# jpwr_v1.net
KiCad netlist of a schematic drawn in EAGLE
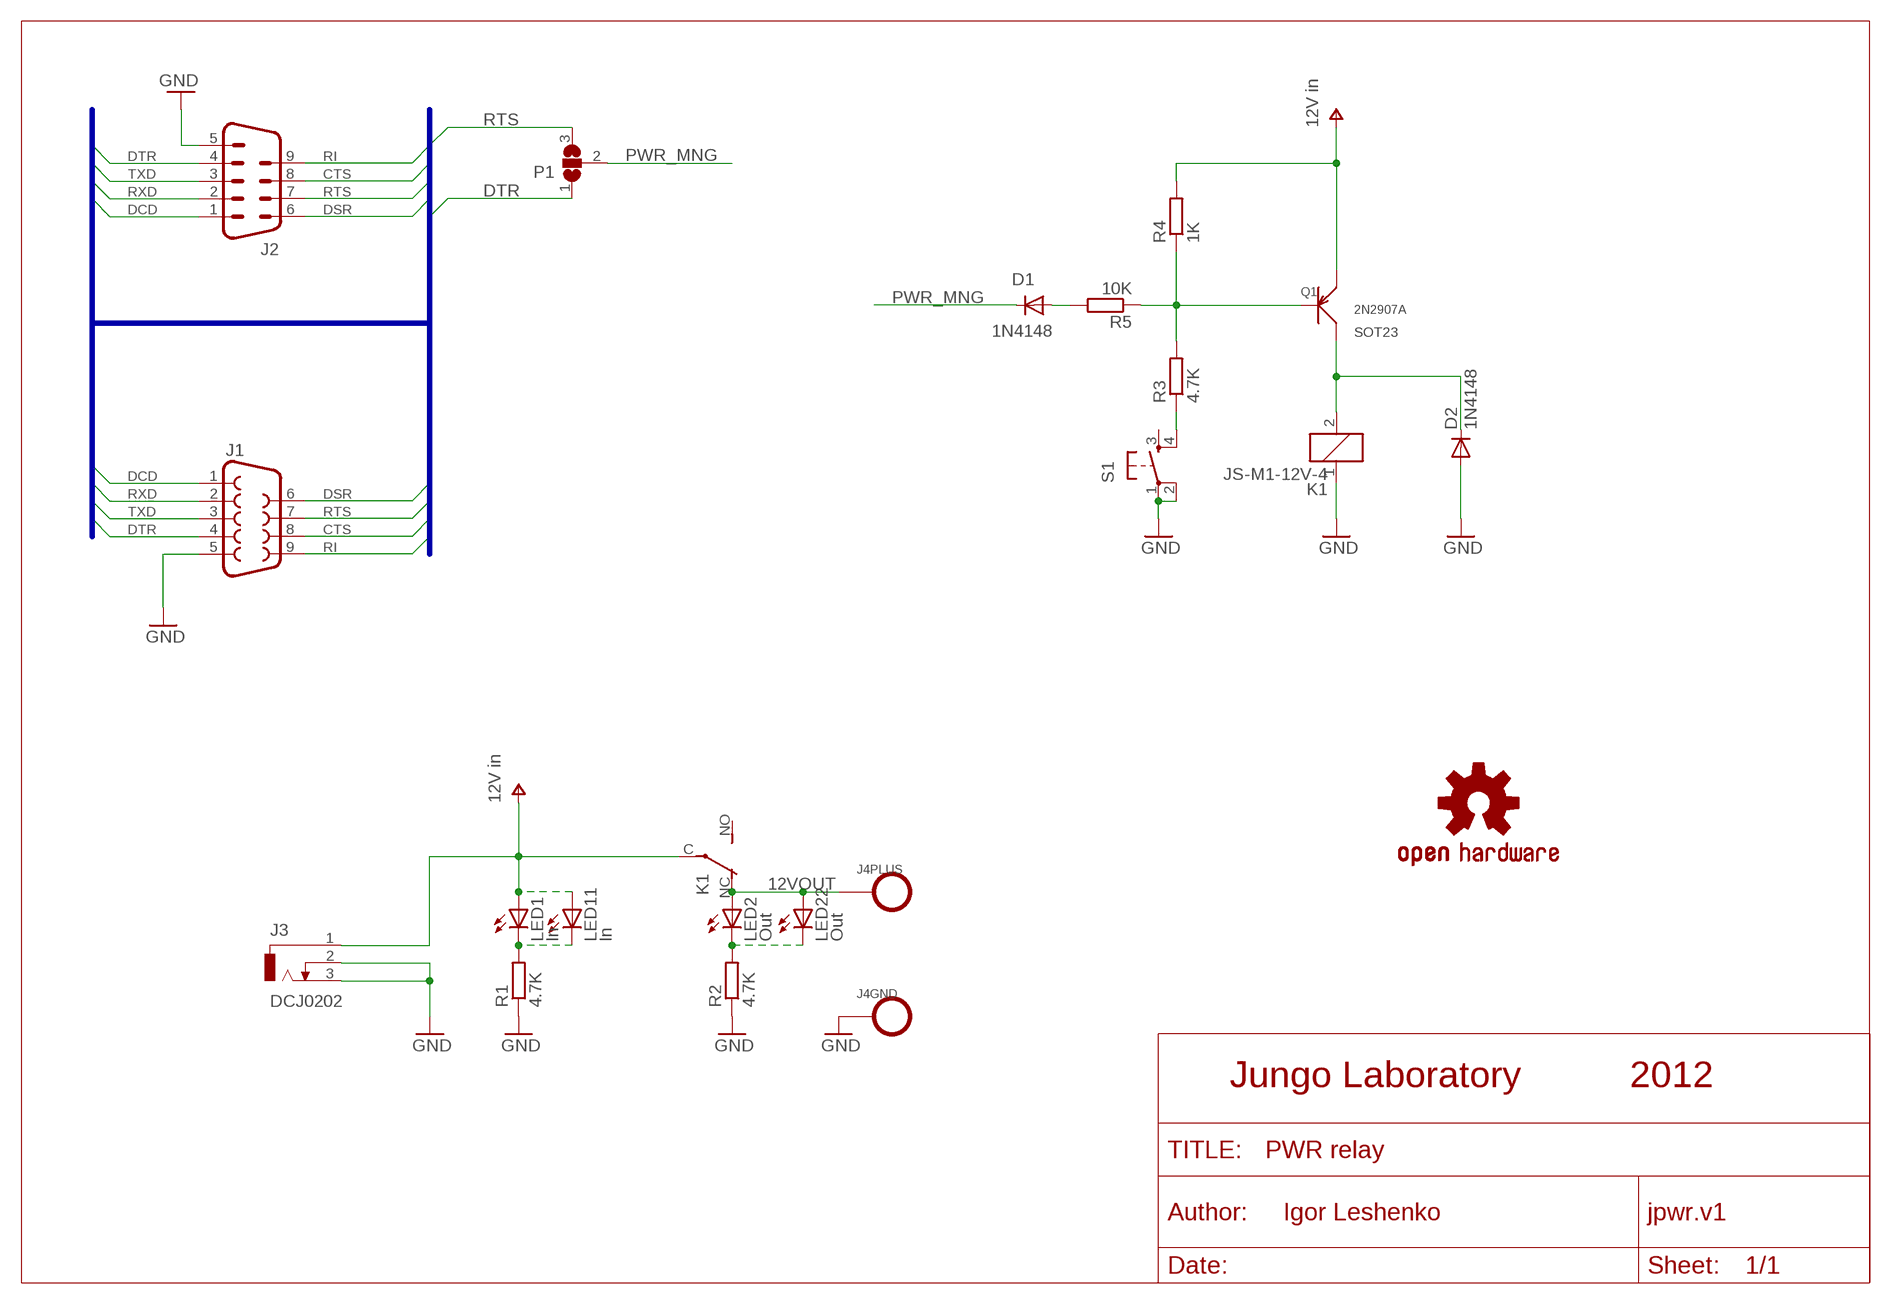
[diagram p0: schematic, sheet 1]

(export (version "E")
  (design (tool "Eeschema 10.0.6"))
  (components
    (comp (ref "D1")
      (value "1N4148")
      (footprint "eagle-import:SOD123")
      (libsource (lib "eagle-import") (part "DIODE-SOD123"))
    )
    (comp (ref "D2")
      (value "1N4148")
      (footprint "eagle-import:SOD123")
      (libsource (lib "eagle-import") (part "DIODE-SOD123"))
    )
    (comp (ref "J1")
      (value "F09D")
      (footprint "eagle-import:F09D")
      (libsource (lib "eagle-import") (part "F09D"))
    )
    (comp (ref "J2")
      (value "M09D")
      (footprint "eagle-import:M09D")
      (libsource (lib "eagle-import") (part "M09D"))
    )
    (comp (ref "J3")
      (value "DCJ0202")
      (footprint "eagle-import:DCJ0202")
      (libsource (lib "eagle-import") (part "DCJ0202"))
    )
    (comp (ref "J4")
      (value "POWER-OUT")
      (footprint "eagle-import:FLEX-POWER")
      (libsource (lib "eagle-import") (part "POWER-OUT"))
    )
    (comp (ref "K1")
      (value "JS-M1-12V-4")
      (footprint "eagle-import:SRD")
      (fields
        (field (name "MPN") "JSM1-12V-4")
        (field (name "MPN_1") "JSM1-12V-4")
        (field (name "OC_FARNELL") "910338")
        (field (name "OC_NEWARK") "13P4552")
      )
      (libsource (lib "eagle-import") (part "JS-M1-12V-4"))
    )
    (comp (ref "LED1")
      (value "In")
      (footprint "eagle-import:CHIP-LED0805")
      (libsource (lib "eagle-import") (part "LEDCHIP-LED0805"))
    )
    (comp (ref "LED2")
      (value "Out")
      (footprint "eagle-import:CHIP-LED0805")
      (libsource (lib "eagle-import") (part "LEDCHIP-LED0805"))
    )
    (comp (ref "LED11")
      (value "In")
      (footprint "eagle-import:CHIP-LED0805")
      (libsource (lib "eagle-import") (part "LEDCHIP-LED0805"))
    )
    (comp (ref "LED22")
      (value "Out")
      (footprint "eagle-import:CHIP-LED0805")
      (libsource (lib "eagle-import") (part "LEDCHIP-LED0805"))
    )
    (comp (ref "P1")
      (value "PAD-SOLDERJUMPER-2WAYT")
      (footprint "eagle-import:3P-SMD-4.8X2")
      (libsource (lib "eagle-import") (part "PAD-SOLDERJUMPER-2WAYT"))
    )
    (comp (ref "Q1")
      (value "2N2907A")
      (footprint "eagle-import:SOT23")
      (libsource (lib "eagle-import") (part "TRANSISTOR-PNP-SOT23"))
    )
    (comp (ref "R1")
      (value "4.7K")
      (footprint "eagle-import:M0805")
      (libsource (lib "eagle-import") (part "R-EU_M0805"))
    )
    (comp (ref "R2")
      (value "4.7K")
      (footprint "eagle-import:M0805")
      (libsource (lib "eagle-import") (part "R-EU_M0805"))
    )
    (comp (ref "R3")
      (value "4.7K")
      (footprint "eagle-import:M0805")
      (libsource (lib "eagle-import") (part "R-EU_M0805"))
    )
    (comp (ref "R4")
      (value "1K")
      (footprint "eagle-import:M0805")
      (libsource (lib "eagle-import") (part "R-EU_M0805"))
    )
    (comp (ref "R5")
      (value "10K")
      (footprint "eagle-import:M0805")
      (libsource (lib "eagle-import") (part "R-EU_M0805"))
    )
    (comp (ref "S1")
      (value "TAC_SWITCHPTH")
      (footprint "eagle-import:TACTILE-PTH")
      (libsource (lib "eagle-import") (part "TAC_SWITCHPTH"))
    )
    (comp (ref "U$1")
      (value "OSHW-LOGOL")
      (footprint "eagle-import:OSHW-LOGO-L")
      (libsource (lib "eagle-import") (part "OSHW-LOGOL"))
    )
  )
  (nets
    (net (code "1") (name "/12VOUT") (class "Default")
      (node (ref "J4") (pin "1") (pinfunction "P$1_1") (pintype "bidirectional"))
      (node (ref "K1") (pin "NC") (pinfunction "O_NC") (pintype "passive"))
      (node (ref "LED2") (pin "A") (pinfunction "A_A") (pintype "passive"))
      (node (ref "LED22") (pin "A") (pinfunction "A_A") (pintype "passive"))
    )
    (net (code "2") (name "/CTS") (class "Default")
      (node (ref "J1") (pin "8") (pinfunction "8_8") (pintype "passive"))
      (node (ref "J2") (pin "8") (pinfunction "8_8") (pintype "passive"))
    )
    (net (code "3") (name "/DCD") (class "Default")
      (node (ref "J1") (pin "1") (pinfunction "1_1") (pintype "passive"))
      (node (ref "J2") (pin "1") (pinfunction "1_1") (pintype "passive"))
    )
    (net (code "4") (name "/DSR") (class "Default")
      (node (ref "J1") (pin "6") (pinfunction "6_6") (pintype "passive"))
      (node (ref "J2") (pin "6") (pinfunction "6_6") (pintype "passive"))
    )
    (net (code "5") (name "/DTR") (class "Default")
      (node (ref "J1") (pin "4") (pinfunction "4_4") (pintype "passive"))
      (node (ref "J2") (pin "4") (pinfunction "4_4") (pintype "passive"))
      (node (ref "P1") (pin "1") (pinfunction "1_1") (pintype "passive"))
    )
    (net (code "6") (name "/PWR_MNG") (class "Default")
      (node (ref "D1") (pin "C") (pinfunction "C_C") (pintype "passive"))
      (node (ref "P1") (pin "2") (pinfunction "2_2") (pintype "passive"))
    )
    (net (code "7") (name "/RI") (class "Default")
      (node (ref "J1") (pin "9") (pinfunction "9_9") (pintype "passive"))
      (node (ref "J2") (pin "9") (pinfunction "9_9") (pintype "passive"))
    )
    (net (code "8") (name "/RTS") (class "Default")
      (node (ref "J1") (pin "7") (pinfunction "7_7") (pintype "passive"))
      (node (ref "J2") (pin "7") (pinfunction "7_7") (pintype "passive"))
      (node (ref "P1") (pin "3") (pinfunction "3_3") (pintype "passive"))
    )
    (net (code "9") (name "/RXD") (class "Default")
      (node (ref "J1") (pin "2") (pinfunction "2_2") (pintype "passive"))
      (node (ref "J2") (pin "2") (pinfunction "2_2") (pintype "passive"))
    )
    (net (code "10") (name "/TXD") (class "Default")
      (node (ref "J1") (pin "3") (pinfunction "3_3") (pintype "passive"))
      (node (ref "J2") (pin "3") (pinfunction "3_3") (pintype "passive"))
    )
    (net (code "11") (name "12V in") (class "Default")
      (node (ref "J3") (pin "1") (pinfunction "1_1") (pintype "passive"))
      (node (ref "K1") (pin "C") (pinfunction "P_C") (pintype "passive"))
      (node (ref "LED1") (pin "A") (pinfunction "A_A") (pintype "passive"))
      (node (ref "LED11") (pin "A") (pinfunction "A_A") (pintype "passive"))
      (node (ref "Q1") (pin "2") (pinfunction "E_2") (pintype "passive"))
      (node (ref "R4") (pin "2") (pinfunction "2_2") (pintype "passive"))
    )
    (net (code "12") (name "GND") (class "Default")
      (node (ref "D2") (pin "A") (pinfunction "A_A") (pintype "passive"))
      (node (ref "J1") (pin "5") (pinfunction "5_5") (pintype "passive"))
      (node (ref "J2") (pin "5") (pinfunction "5_5") (pintype "passive"))
      (node (ref "J3") (pin "2") (pinfunction "2_2") (pintype "passive"))
      (node (ref "J3") (pin "3") (pinfunction "3_3") (pintype "passive"))
      (node (ref "J4") (pin "2") (pinfunction "P$1_2") (pintype "bidirectional"))
      (node (ref "K1") (pin "1") (pinfunction "1_1") (pintype "passive"))
      (node (ref "R1") (pin "1") (pinfunction "1_1") (pintype "passive"))
      (node (ref "R2") (pin "1") (pinfunction "1_1") (pintype "passive"))
      (node (ref "S1") (pin "1") (pinfunction "1_1") (pintype "passive"))
      (node (ref "S1") (pin "2") (pinfunction "2_2") (pintype "passive"))
    )
    (net (code "13") (name "Net-(D1-PadA)") (class "Default")
      (node (ref "D1") (pin "A") (pinfunction "A_A") (pintype "passive"))
      (node (ref "R5") (pin "2") (pinfunction "2_2") (pintype "passive"))
    )
    (net (code "14") (name "Net-(LED1-PadC)") (class "Default")
      (node (ref "LED1") (pin "C") (pinfunction "C_C") (pintype "passive"))
      (node (ref "LED11") (pin "C") (pinfunction "C_C") (pintype "passive"))
      (node (ref "R1") (pin "2") (pinfunction "2_2") (pintype "passive"))
    )
    (net (code "15") (name "Net-(LED2-PadC)") (class "Default")
      (node (ref "LED2") (pin "C") (pinfunction "C_C") (pintype "passive"))
      (node (ref "LED22") (pin "C") (pinfunction "C_C") (pintype "passive"))
      (node (ref "R2") (pin "2") (pinfunction "2_2") (pintype "passive"))
    )
    (net (code "16") (name "Net-(Q1-B)") (class "Default")
      (node (ref "Q1") (pin "1") (pinfunction "B_1") (pintype "passive"))
      (node (ref "R3") (pin "2") (pinfunction "2_2") (pintype "passive"))
      (node (ref "R4") (pin "1") (pinfunction "1_1") (pintype "passive"))
      (node (ref "R5") (pin "1") (pinfunction "1_1") (pintype "passive"))
    )
    (net (code "17") (name "Net-(Q1-C)") (class "Default")
      (node (ref "D2") (pin "C") (pinfunction "C_C") (pintype "passive"))
      (node (ref "K1") (pin "2") (pinfunction "2_2") (pintype "passive"))
      (node (ref "Q1") (pin "3") (pinfunction "C_3") (pintype "passive"))
    )
    (net (code "18") (name "Net-(R3-Pad1)") (class "Default")
      (node (ref "R3") (pin "1") (pinfunction "1_1") (pintype "passive"))
      (node (ref "S1") (pin "4") (pinfunction "4_4") (pintype "passive"))
    )
    (net (code "19") (name "unconnected-(K1B-S-PadNO)") (class "Default")
      (node (ref "K1") (pin "NO") (pinfunction "S_NO") (pintype "passive"))
    )
    (net (code "20") (name "unconnected-(S1-Pad3)") (class "Default")
      (node (ref "S1") (pin "3") (pinfunction "3_3") (pintype "passive"))
    )
  )
)
